# LED_control.net
KiCad netlist of a schematic drawn in EAGLE
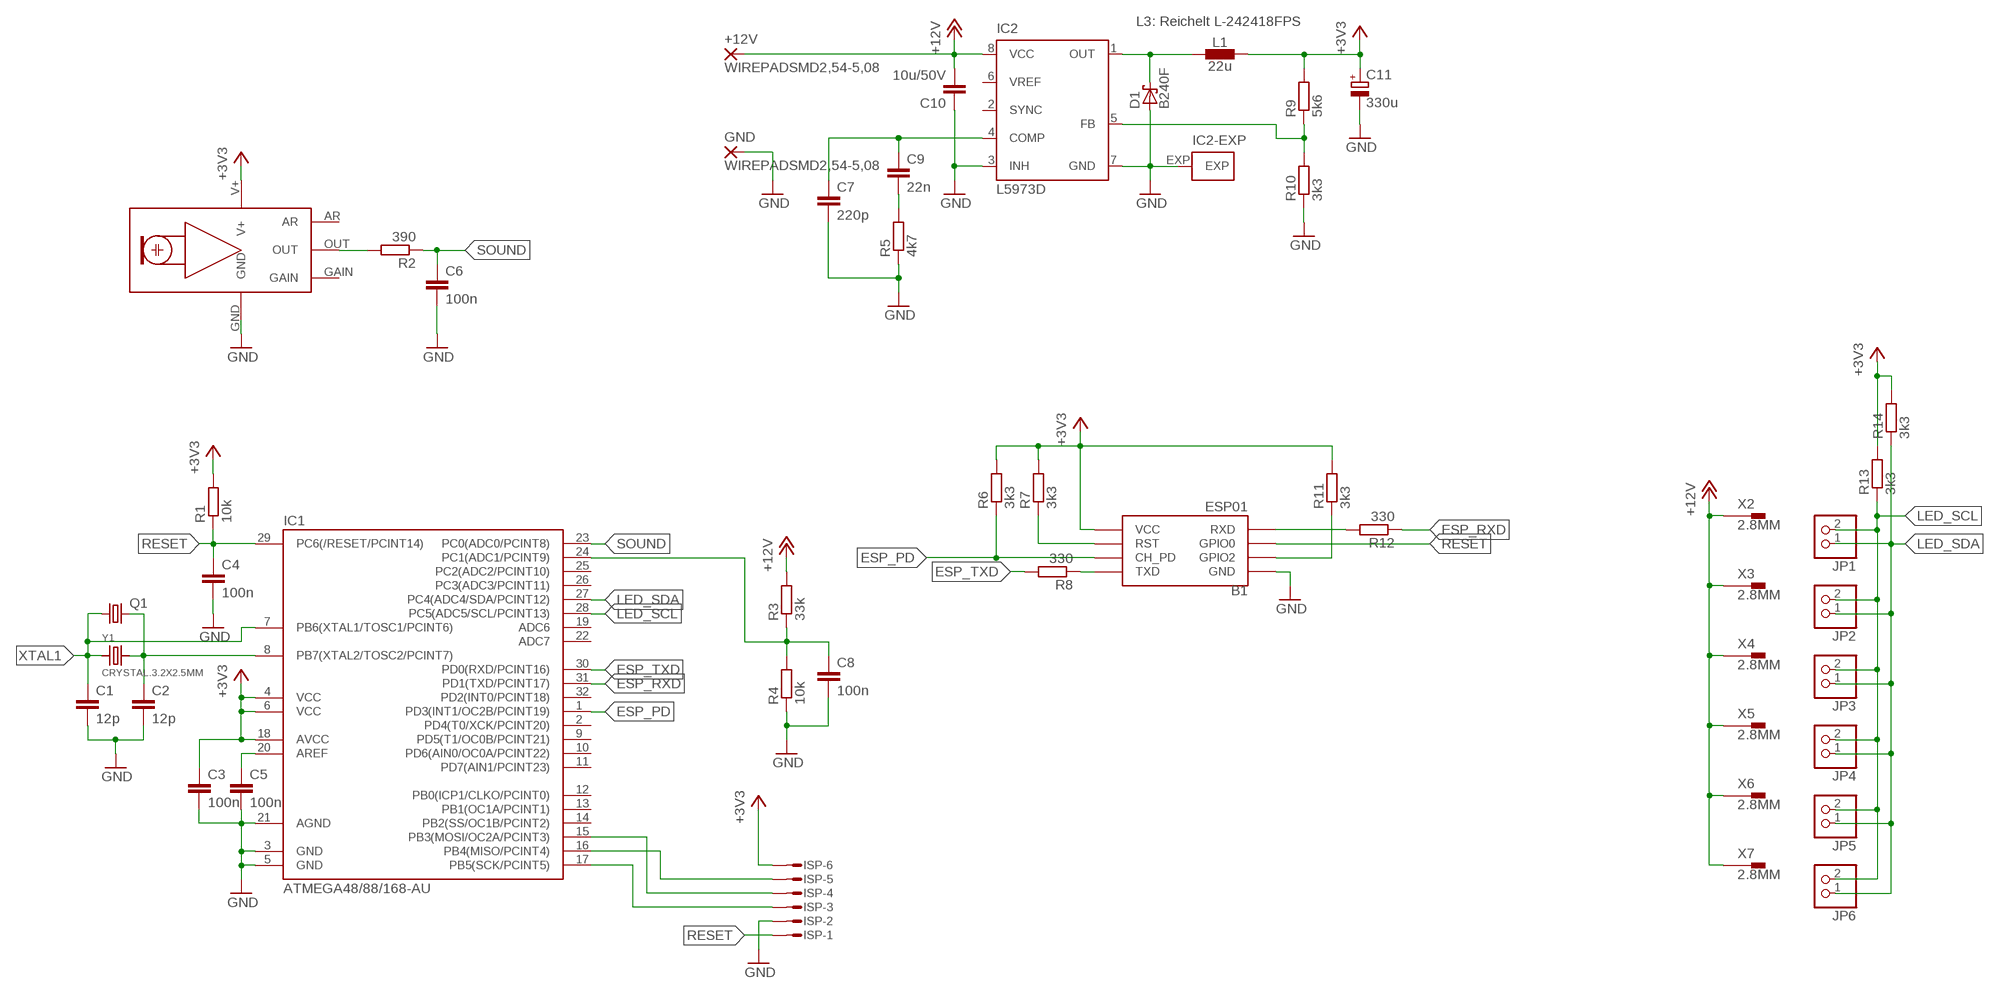
[diagram p0: schematic, sheet 1]

(export (version "E")
  (design (tool "Eeschema 10.0.6"))
  (components
    (comp (ref "+12V")
      (value "WIREPADSMD2,54-5,08")
      (footprint "eagle-import:SMD2,54-5,08")
      (libsource (lib "eagle-import") (part "WIREPADSMD2,54-5,08"))
    )
    (comp (ref "B1")
      (value "ESP01")
      (footprint "eagle-import:ESP01")
      (libsource (lib "eagle-import") (part "ESP01"))
    )
    (comp (ref "C1")
      (value "12p")
      (footprint "eagle-import:C0603K")
      (libsource (lib "eagle-import") (part "C-EUC0603K"))
    )
    (comp (ref "C2")
      (value "12p")
      (footprint "eagle-import:C0603K")
      (libsource (lib "eagle-import") (part "C-EUC0603K"))
    )
    (comp (ref "C3")
      (value "100n")
      (footprint "eagle-import:C0603K")
      (libsource (lib "eagle-import") (part "resistor_C-EUC0603K"))
    )
    (comp (ref "C4")
      (value "100n")
      (footprint "eagle-import:C0603")
      (libsource (lib "eagle-import") (part "resistor_C-EUC0603"))
    )
    (comp (ref "C5")
      (value "100n")
      (footprint "eagle-import:C0603K")
      (libsource (lib "eagle-import") (part "resistor_C-EUC0603K"))
    )
    (comp (ref "C6")
      (value "100n")
      (footprint "eagle-import:C0603K")
      (libsource (lib "eagle-import") (part "resistor_C-EUC0603K"))
    )
    (comp (ref "C7")
      (value "220p")
      (footprint "eagle-import:C0603")
      (libsource (lib "eagle-import") (part "C-EUC0603"))
    )
    (comp (ref "C8")
      (value "100n")
      (footprint "eagle-import:C0603")
      (libsource (lib "eagle-import") (part "resistor_C-EUC0603"))
    )
    (comp (ref "C9")
      (value "22n")
      (footprint "eagle-import:C0603")
      (libsource (lib "eagle-import") (part "C-EUC0603"))
    )
    (comp (ref "C10")
      (value "10u/50V")
      (footprint "eagle-import:C1206")
      (libsource (lib "eagle-import") (part "C-EUC1206"))
    )
    (comp (ref "C11")
      (value "330u")
      (footprint "eagle-import:153CLV-0605")
      (libsource (lib "eagle-import") (part "CPOL-EU153CLV-0605"))
    )
    (comp (ref "D1")
      (value "B240F")
      (footprint "eagle-import:SMB")
      (libsource (lib "eagle-import") (part "SCHOTTKY-DIODESMD"))
    )
    (comp (ref "GND")
      (value "WIREPADSMD2,54-5,08")
      (footprint "eagle-import:SMD2,54-5,08")
      (libsource (lib "eagle-import") (part "WIREPADSMD2,54-5,08"))
    )
    (comp (ref "IC1")
      (value "ATMEGA48/88/168-AU")
      (footprint "eagle-import:TQFP32-08")
      (libsource (lib "eagle-import") (part "ATMEGA48/88/168-AU"))
    )
    (comp (ref "IC2")
      (value "L5973D")
      (footprint "eagle-import:HSOP8")
      (fields (field (name "MF") "STMICROELECTRONICS"))
      (libsource (lib "eagle-import") (part "L5973D"))
    )
    (comp (ref "ISP")
      (value "MICROMATCH-6SMF")
      (footprint "eagle-import:MMT-F-SMD-6")
      (libsource (lib "eagle-import") (part "MICROMATCH-6SMF"))
    )
    (comp (ref "JP1")
      (value "PINHD-1X2/90")
      (footprint "eagle-import:1X02_90")
      (libsource (lib "eagle-import") (part "PINHD-1X2/90"))
    )
    (comp (ref "JP2")
      (value "PINHD-1X2/90")
      (footprint "eagle-import:1X02_90")
      (libsource (lib "eagle-import") (part "PINHD-1X2/90"))
    )
    (comp (ref "JP3")
      (value "PINHD-1X2/90")
      (footprint "eagle-import:1X02_90")
      (libsource (lib "eagle-import") (part "PINHD-1X2/90"))
    )
    (comp (ref "JP4")
      (value "PINHD-1X2/90")
      (footprint "eagle-import:1X02_90")
      (libsource (lib "eagle-import") (part "PINHD-1X2/90"))
    )
    (comp (ref "JP5")
      (value "PINHD-1X2/90")
      (footprint "eagle-import:1X02_90")
      (libsource (lib "eagle-import") (part "PINHD-1X2/90"))
    )
    (comp (ref "JP6")
      (value "PINHD-1X2/90")
      (footprint "eagle-import:1X02_90")
      (libsource (lib "eagle-import") (part "PINHD-1X2/90"))
    )
    (comp (ref "L1")
      (value "22u")
      (footprint "eagle-import:L_NR60XX")
      (libsource (lib "eagle-import") (part "INDUCTOR-NR60XX"))
    )
    (comp (ref "PCB1")
      (value "MAX9814_AGC_MIC")
      (footprint "eagle-import:MAX9814_AGC_MIC")
      (libsource (lib "eagle-import") (part "MAX9814_AGC_MIC"))
    )
    (comp (ref "Q1")
      (value "CRYSTALHC49S")
      (footprint "eagle-import:HC49_S")
      (libsource (lib "eagle-import") (part "CRYSTALHC49S"))
    )
    (comp (ref "R1")
      (value "10k")
      (footprint "eagle-import:R0603")
      (libsource (lib "eagle-import") (part "R-EU_R0603"))
    )
    (comp (ref "R2")
      (value "390")
      (footprint "eagle-import:R0603")
      (libsource (lib "eagle-import") (part "R-EU_R0603"))
    )
    (comp (ref "R3")
      (value "33k")
      (footprint "eagle-import:R0603")
      (libsource (lib "eagle-import") (part "R-EU_R0603"))
    )
    (comp (ref "R4")
      (value "10k")
      (footprint "eagle-import:R0603")
      (libsource (lib "eagle-import") (part "R-EU_R0603"))
    )
    (comp (ref "R5")
      (value "4k7")
      (footprint "eagle-import:R0603")
      (libsource (lib "eagle-import") (part "R-EU_R0603"))
    )
    (comp (ref "R6")
      (value "3k3")
      (footprint "eagle-import:R0603")
      (libsource (lib "eagle-import") (part "R-EU_R0603"))
    )
    (comp (ref "R7")
      (value "3k3")
      (footprint "eagle-import:R0603")
      (libsource (lib "eagle-import") (part "R-EU_R0603"))
    )
    (comp (ref "R8")
      (value "330")
      (footprint "eagle-import:R0603")
      (libsource (lib "eagle-import") (part "R-EU_R0603"))
    )
    (comp (ref "R9")
      (value "5k6")
      (footprint "eagle-import:R0603")
      (libsource (lib "eagle-import") (part "R-EU_R0603"))
    )
    (comp (ref "R10")
      (value "3k3")
      (footprint "eagle-import:R0603")
      (libsource (lib "eagle-import") (part "R-EU_R0603"))
    )
    (comp (ref "R11")
      (value "3k3")
      (footprint "eagle-import:R0603")
      (libsource (lib "eagle-import") (part "R-EU_R0603"))
    )
    (comp (ref "R12")
      (value "330")
      (footprint "eagle-import:R0603")
      (libsource (lib "eagle-import") (part "R-EU_R0603"))
    )
    (comp (ref "R13")
      (value "3k3")
      (footprint "eagle-import:R0603")
      (libsource (lib "eagle-import") (part "R-EU_R0603"))
    )
    (comp (ref "R14")
      (value "3k3")
      (footprint "eagle-import:R0603")
      (libsource (lib "eagle-import") (part "R-EU_R0603"))
    )
    (comp (ref "X2")
      (value "2.8MM")
      (footprint "eagle-import:2.8_90")
      (libsource (lib "eagle-import") (part "2.8MM"))
    )
    (comp (ref "X3")
      (value "2.8MM")
      (footprint "eagle-import:2.8_90")
      (libsource (lib "eagle-import") (part "2.8MM"))
    )
    (comp (ref "X4")
      (value "2.8MM")
      (footprint "eagle-import:2.8_90")
      (libsource (lib "eagle-import") (part "2.8MM"))
    )
    (comp (ref "X5")
      (value "2.8MM")
      (footprint "eagle-import:2.8_90")
      (libsource (lib "eagle-import") (part "2.8MM"))
    )
    (comp (ref "X6")
      (value "2.8MM")
      (footprint "eagle-import:2.8_90")
      (libsource (lib "eagle-import") (part "2.8MM"))
    )
    (comp (ref "X7")
      (value "2.8MM")
      (footprint "eagle-import:2.8_90")
      (libsource (lib "eagle-import") (part "2.8MM"))
    )
    (comp (ref "Y1")
      (value "CRYSTAL.3.2X2.5MM")
      (footprint "eagle-import:3.2X2.5MM")
      (libsource (lib "eagle-import") (part "CRYSTAL.3.2X2.5MM"))
    )
  )
  (nets
    (net (code "1") (name "+3V3") (class "Default")
      (node (ref "B1") (pin "VCC") (pinfunction "VCC_VCC") (pintype "bidirectional"))
      (node (ref "C11") (pin "+") (pinfunction "+_+") (pintype "passive"))
      (node (ref "C3") (pin "1") (pinfunction "1_1") (pintype "passive"))
      (node (ref "IC1") (pin "18") (pinfunction "AVCC_18") (pintype "passive"))
      (node (ref "IC1") (pin "4") (pinfunction "VCC_4") (pintype "power_in"))
      (node (ref "IC1") (pin "6") (pinfunction "VCC_6") (pintype "power_in"))
      (node (ref "ISP") (pin "6") (pinfunction "S_6") (pintype "passive"))
      (node (ref "L1") (pin "2") (pinfunction "2_2") (pintype "passive"))
      (node (ref "PCB1") (pin "V+") (pinfunction "V+_V+") (pintype "bidirectional"))
      (node (ref "R1") (pin "2") (pinfunction "2_2") (pintype "passive"))
      (node (ref "R11") (pin "2") (pinfunction "2_2") (pintype "passive"))
      (node (ref "R13") (pin "2") (pinfunction "2_2") (pintype "passive"))
      (node (ref "R14") (pin "2") (pinfunction "2_2") (pintype "passive"))
      (node (ref "R6") (pin "2") (pinfunction "2_2") (pintype "passive"))
      (node (ref "R7") (pin "2") (pinfunction "2_2") (pintype "passive"))
      (node (ref "R9") (pin "2") (pinfunction "2_2") (pintype "passive"))
    )
    (net (code "2") (name "+12V") (class "Default")
      (node (ref "+12V") (pin "1") (pinfunction "P_1") (pintype "passive"))
      (node (ref "C10") (pin "2") (pinfunction "2_2") (pintype "passive"))
      (node (ref "IC2") (pin "8") (pinfunction "VCC_8") (pintype "input"))
      (node (ref "R3") (pin "2") (pinfunction "2_2") (pintype "passive"))
      (node (ref "X2") (pin "1A") (pinfunction "1_1A") (pintype "passive"))
      (node (ref "X2") (pin "1B") (pinfunction "1_1B") (pintype "passive"))
      (node (ref "X3") (pin "1A") (pinfunction "1_1A") (pintype "passive"))
      (node (ref "X3") (pin "1B") (pinfunction "1_1B") (pintype "passive"))
      (node (ref "X4") (pin "1A") (pinfunction "1_1A") (pintype "passive"))
      (node (ref "X4") (pin "1B") (pinfunction "1_1B") (pintype "passive"))
      (node (ref "X5") (pin "1A") (pinfunction "1_1A") (pintype "passive"))
      (node (ref "X5") (pin "1B") (pinfunction "1_1B") (pintype "passive"))
      (node (ref "X6") (pin "1A") (pinfunction "1_1A") (pintype "passive"))
      (node (ref "X6") (pin "1B") (pinfunction "1_1B") (pintype "passive"))
      (node (ref "X7") (pin "1A") (pinfunction "1_1A") (pintype "passive"))
      (node (ref "X7") (pin "1B") (pinfunction "1_1B") (pintype "passive"))
    )
    (net (code "3") (name "ESP_PD") (class "Default")
      (node (ref "B1") (pin "CH_PD") (pinfunction "CH_PD_CH_PD") (pintype "bidirectional"))
      (node (ref "IC1") (pin "1") (pinfunction "PD3(INT1/OC2B/PCINT19)_1") (pintype "bidirectional"))
      (node (ref "R6") (pin "1") (pinfunction "1_1") (pintype "passive"))
    )
    (net (code "4") (name "ESP_RXD") (class "Default")
      (node (ref "IC1") (pin "31") (pinfunction "PD1(TXD/PCINT17)_31") (pintype "bidirectional"))
      (node (ref "R12") (pin "1") (pinfunction "1_1") (pintype "passive"))
    )
    (net (code "5") (name "ESP_TXD") (class "Default")
      (node (ref "IC1") (pin "30") (pinfunction "PD0(RXD/PCINT16)_30") (pintype "bidirectional"))
      (node (ref "R8") (pin "2") (pinfunction "2_2") (pintype "passive"))
    )
    (net (code "6") (name "GND") (class "Default")
      (node (ref "B1") (pin "GND") (pinfunction "GND_GND") (pintype "bidirectional"))
      (node (ref "C1") (pin "2") (pinfunction "2_2") (pintype "passive"))
      (node (ref "C10") (pin "1") (pinfunction "1_1") (pintype "passive"))
      (node (ref "C11") (pin "-") (pinfunction "-_-") (pintype "passive"))
      (node (ref "C2") (pin "2") (pinfunction "2_2") (pintype "passive"))
      (node (ref "C3") (pin "2") (pinfunction "2_2") (pintype "passive"))
      (node (ref "C4") (pin "2") (pinfunction "2_2") (pintype "passive"))
      (node (ref "C5") (pin "2") (pinfunction "2_2") (pintype "passive"))
      (node (ref "C6") (pin "2") (pinfunction "2_2") (pintype "passive"))
      (node (ref "C7") (pin "2") (pinfunction "2_2") (pintype "passive"))
      (node (ref "C8") (pin "2") (pinfunction "2_2") (pintype "passive"))
      (node (ref "D1") (pin "A") (pinfunction "A_A") (pintype "passive"))
      (node (ref "GND") (pin "1") (pinfunction "P_1") (pintype "passive"))
      (node (ref "IC1") (pin "21") (pinfunction "AGND_21") (pintype "power_in"))
      (node (ref "IC1") (pin "3") (pinfunction "GND_3") (pintype "power_in"))
      (node (ref "IC1") (pin "5") (pinfunction "GND_5") (pintype "power_in"))
      (node (ref "IC2") (pin "3") (pinfunction "INH_3") (pintype "input"))
      (node (ref "IC2") (pin "7") (pinfunction "GND_7") (pintype "power_in"))
      (node (ref "IC2") (pin "EXP") (pinfunction "EXP_EXP") (pintype "input"))
      (node (ref "ISP") (pin "2") (pinfunction "S_2") (pintype "passive"))
      (node (ref "PCB1") (pin "GND") (pinfunction "GND_GND") (pintype "bidirectional"))
      (node (ref "R10") (pin "1") (pinfunction "1_1") (pintype "passive"))
      (node (ref "R4") (pin "1") (pinfunction "1_1") (pintype "passive"))
      (node (ref "R5") (pin "1") (pinfunction "1_1") (pintype "passive"))
    )
    (net (code "7") (name "LED_SCL") (class "Default")
      (node (ref "IC1") (pin "28") (pinfunction "PC5(ADC5/SCL/PCINT13)_28") (pintype "bidirectional"))
      (node (ref "JP1") (pin "2") (pinfunction "2_2") (pintype "passive"))
      (node (ref "JP2") (pin "2") (pinfunction "2_2") (pintype "passive"))
      (node (ref "JP3") (pin "2") (pinfunction "2_2") (pintype "passive"))
      (node (ref "JP4") (pin "2") (pinfunction "2_2") (pintype "passive"))
      (node (ref "JP5") (pin "2") (pinfunction "2_2") (pintype "passive"))
      (node (ref "JP6") (pin "2") (pinfunction "2_2") (pintype "passive"))
      (node (ref "R13") (pin "1") (pinfunction "1_1") (pintype "passive"))
    )
    (net (code "8") (name "LED_SDA") (class "Default")
      (node (ref "IC1") (pin "27") (pinfunction "PC4(ADC4/SDA/PCINT12)_27") (pintype "bidirectional"))
      (node (ref "JP1") (pin "1") (pinfunction "1_1") (pintype "passive"))
      (node (ref "JP2") (pin "1") (pinfunction "1_1") (pintype "passive"))
      (node (ref "JP3") (pin "1") (pinfunction "1_1") (pintype "passive"))
      (node (ref "JP4") (pin "1") (pinfunction "1_1") (pintype "passive"))
      (node (ref "JP5") (pin "1") (pinfunction "1_1") (pintype "passive"))
      (node (ref "JP6") (pin "1") (pinfunction "1_1") (pintype "passive"))
      (node (ref "R14") (pin "1") (pinfunction "1_1") (pintype "passive"))
    )
    (net (code "9") (name "Net-(B1-PadGPIO2)") (class "Default")
      (node (ref "B1") (pin "GPIO2") (pinfunction "GPIO2_GPIO2") (pintype "bidirectional"))
      (node (ref "R11") (pin "1") (pinfunction "1_1") (pintype "passive"))
    )
    (net (code "10") (name "Net-(B1-PadRST)") (class "Default")
      (node (ref "B1") (pin "RST") (pinfunction "RST_RST") (pintype "bidirectional"))
      (node (ref "R7") (pin "1") (pinfunction "1_1") (pintype "passive"))
    )
    (net (code "11") (name "Net-(B1-RXD)") (class "Default")
      (node (ref "B1") (pin "RX") (pinfunction "RXD_RX") (pintype "bidirectional"))
      (node (ref "R12") (pin "2") (pinfunction "2_2") (pintype "passive"))
    )
    (net (code "12") (name "Net-(B1-TXD)") (class "Default")
      (node (ref "B1") (pin "TX") (pinfunction "TXD_TX") (pintype "bidirectional"))
      (node (ref "R8") (pin "1") (pinfunction "1_1") (pintype "passive"))
    )
    (net (code "13") (name "Net-(C9-Pad2)") (class "Default")
      (node (ref "C9") (pin "2") (pinfunction "2_2") (pintype "passive"))
      (node (ref "R5") (pin "2") (pinfunction "2_2") (pintype "passive"))
    )
    (net (code "14") (name "Net-(IC1-AREF)") (class "Default")
      (node (ref "C5") (pin "1") (pinfunction "1_1") (pintype "passive"))
      (node (ref "IC1") (pin "20") (pinfunction "AREF_20") (pintype "passive"))
    )
    (net (code "15") (name "Net-(IC1-PB3(MOSI{slash}OC2A{slash}PCINT3))") (class "Default")
      (node (ref "IC1") (pin "15") (pinfunction "PB3(MOSI/OC2A/PCINT3)_15") (pintype "bidirectional"))
      (node (ref "ISP") (pin "4") (pinfunction "S_4") (pintype "passive"))
    )
    (net (code "16") (name "Net-(IC1-PB4(MISO{slash}PCINT4))") (class "Default")
      (node (ref "IC1") (pin "16") (pinfunction "PB4(MISO/PCINT4)_16") (pintype "bidirectional"))
      (node (ref "ISP") (pin "5") (pinfunction "S_5") (pintype "passive"))
    )
    (net (code "17") (name "Net-(IC1-PB5(SCK{slash}PCINT5))") (class "Default")
      (node (ref "IC1") (pin "17") (pinfunction "PB5(SCK/PCINT5)_17") (pintype "bidirectional"))
      (node (ref "ISP") (pin "3") (pinfunction "S_3") (pintype "passive"))
    )
    (net (code "18") (name "Net-(IC1-PB7(XTAL2{slash}TOSC2{slash}PCINT7))") (class "Default")
      (node (ref "C2") (pin "1") (pinfunction "1_1") (pintype "passive"))
      (node (ref "IC1") (pin "8") (pinfunction "PB7(XTAL2/TOSC2/PCINT7)_8") (pintype "bidirectional"))
      (node (ref "Q1") (pin "2") (pinfunction "2_2") (pintype "passive"))
      (node (ref "Y1") (pin "3") (pinfunction "2_3") (pintype "passive"))
    )
    (net (code "19") (name "Net-(IC1-PC1(ADC1{slash}PCINT9))") (class "Default")
      (node (ref "C8") (pin "1") (pinfunction "1_1") (pintype "passive"))
      (node (ref "IC1") (pin "24") (pinfunction "PC1(ADC1/PCINT9)_24") (pintype "bidirectional"))
      (node (ref "R3") (pin "1") (pinfunction "1_1") (pintype "passive"))
      (node (ref "R4") (pin "2") (pinfunction "2_2") (pintype "passive"))
    )
    (net (code "20") (name "Net-(IC2B-COMP)") (class "Default")
      (node (ref "C7") (pin "1") (pinfunction "1_1") (pintype "passive"))
      (node (ref "C9") (pin "1") (pinfunction "1_1") (pintype "passive"))
      (node (ref "IC2") (pin "4") (pinfunction "COMP_4") (pintype "passive"))
    )
    (net (code "21") (name "Net-(IC2B-FB)") (class "Default")
      (node (ref "IC2") (pin "5") (pinfunction "FB_5") (pintype "input"))
      (node (ref "R10") (pin "2") (pinfunction "2_2") (pintype "passive"))
      (node (ref "R9") (pin "1") (pinfunction "1_1") (pintype "passive"))
    )
    (net (code "22") (name "Net-(IC2B-OUT)") (class "Default")
      (node (ref "D1") (pin "C") (pinfunction "C_C") (pintype "passive"))
      (node (ref "IC2") (pin "1") (pinfunction "OUT_1") (pintype "output"))
      (node (ref "L1") (pin "1") (pinfunction "1_1") (pintype "passive"))
    )
    (net (code "23") (name "Net-(PCB1-PadOUT)") (class "Default")
      (node (ref "PCB1") (pin "OUT") (pinfunction "OUT_OUT") (pintype "bidirectional"))
      (node (ref "R2") (pin "2") (pinfunction "2_2") (pintype "passive"))
    )
    (net (code "24") (name "RESET") (class "Default")
      (node (ref "B1") (pin "GPIO0") (pinfunction "GPIO0_GPIO0") (pintype "bidirectional"))
      (node (ref "C4") (pin "1") (pinfunction "1_1") (pintype "passive"))
      (node (ref "IC1") (pin "29") (pinfunction "PC6(/RESET/PCINT14)_29") (pintype "bidirectional"))
      (node (ref "ISP") (pin "1") (pinfunction "S_1") (pintype "passive"))
      (node (ref "R1") (pin "1") (pinfunction "1_1") (pintype "passive"))
    )
    (net (code "25") (name "SOUND") (class "Default")
      (node (ref "C6") (pin "1") (pinfunction "1_1") (pintype "passive"))
      (node (ref "IC1") (pin "23") (pinfunction "PC0(ADC0/PCINT8)_23") (pintype "bidirectional"))
      (node (ref "R2") (pin "1") (pinfunction "1_1") (pintype "passive"))
    )
    (net (code "26") (name "XTAL1") (class "Default")
      (node (ref "C1") (pin "1") (pinfunction "1_1") (pintype "passive"))
      (node (ref "IC1") (pin "7") (pinfunction "PB6(XTAL1/TOSC1/PCINT6)_7") (pintype "bidirectional"))
      (node (ref "Q1") (pin "1") (pinfunction "1_1") (pintype "passive"))
      (node (ref "Y1") (pin "1") (pinfunction "1_1") (pintype "passive"))
    )
    (net (code "27") (name "unconnected-(IC1-ADC6-Pad19)") (class "Default")
      (node (ref "IC1") (pin "19") (pinfunction "ADC6_19") (pintype "passive"))
    )
    (net (code "28") (name "unconnected-(IC1-ADC7-Pad22)") (class "Default")
      (node (ref "IC1") (pin "22") (pinfunction "ADC7_22") (pintype "passive"))
    )
    (net (code "29") (name "unconnected-(IC1-PB0(ICP1{slash}CLKO{slash}PCINT0)-Pad12)") (class "Default")
      (node (ref "IC1") (pin "12") (pinfunction "PB0(ICP1/CLKO/PCINT0)_12") (pintype "bidirectional"))
    )
    (net (code "30") (name "unconnected-(IC1-PB1(OC1A{slash}PCINT1)-Pad13)") (class "Default")
      (node (ref "IC1") (pin "13") (pinfunction "PB1(OC1A/PCINT1)_13") (pintype "bidirectional"))
    )
    (net (code "31") (name "unconnected-(IC1-PB2(SS{slash}OC1B{slash}PCINT2)-Pad14)") (class "Default")
      (node (ref "IC1") (pin "14") (pinfunction "PB2(SS/OC1B/PCINT2)_14") (pintype "bidirectional"))
    )
    (net (code "32") (name "unconnected-(IC1-PC2(ADC2{slash}PCINT10)-Pad25)") (class "Default")
      (node (ref "IC1") (pin "25") (pinfunction "PC2(ADC2/PCINT10)_25") (pintype "bidirectional"))
    )
    (net (code "33") (name "unconnected-(IC1-PC3(ADC3{slash}PCINT11)-Pad26)") (class "Default")
      (node (ref "IC1") (pin "26") (pinfunction "PC3(ADC3/PCINT11)_26") (pintype "bidirectional"))
    )
    (net (code "34") (name "unconnected-(IC1-PD2(INT0{slash}PCINT18)-Pad32)") (class "Default")
      (node (ref "IC1") (pin "32") (pinfunction "PD2(INT0/PCINT18)_32") (pintype "bidirectional"))
    )
    (net (code "35") (name "unconnected-(IC1-PD4(T0{slash}XCK{slash}PCINT20)-Pad2)") (class "Default")
      (node (ref "IC1") (pin "2") (pinfunction "PD4(T0/XCK/PCINT20)_2") (pintype "bidirectional"))
    )
    (net (code "36") (name "unconnected-(IC1-PD5(T1{slash}OC0B{slash}PCINT21)-Pad9)") (class "Default")
      (node (ref "IC1") (pin "9") (pinfunction "PD5(T1/OC0B/PCINT21)_9") (pintype "bidirectional"))
    )
    (net (code "37") (name "unconnected-(IC1-PD6(AIN0{slash}OC0A{slash}PCINT22)-Pad10)") (class "Default")
      (node (ref "IC1") (pin "10") (pinfunction "PD6(AIN0/OC0A/PCINT22)_10") (pintype "bidirectional"))
    )
    (net (code "38") (name "unconnected-(IC1-PD7(AIN1{slash}PCINT23)-Pad11)") (class "Default")
      (node (ref "IC1") (pin "11") (pinfunction "PD7(AIN1/PCINT23)_11") (pintype "bidirectional"))
    )
    (net (code "39") (name "unconnected-(IC2B-SYNC-Pad2)") (class "Default")
      (node (ref "IC2") (pin "2") (pinfunction "SYNC_2") (pintype "input"))
    )
    (net (code "40") (name "unconnected-(IC2B-VREF-Pad6)") (class "Default")
      (node (ref "IC2") (pin "6") (pinfunction "VREF_6") (pintype "input"))
    )
    (net (code "41") (name "unconnected-(PCB1-PadAR)") (class "Default")
      (node (ref "PCB1") (pin "AR") (pinfunction "AR_AR") (pintype "bidirectional"))
    )
    (net (code "42") (name "unconnected-(PCB1-PadGAIN)") (class "Default")
      (node (ref "PCB1") (pin "GAIN") (pinfunction "GAIN_GAIN") (pintype "bidirectional"))
    )
  )
)
